# cyclops_r3p1.net
KiCad netlist of a schematic drawn in EAGLE
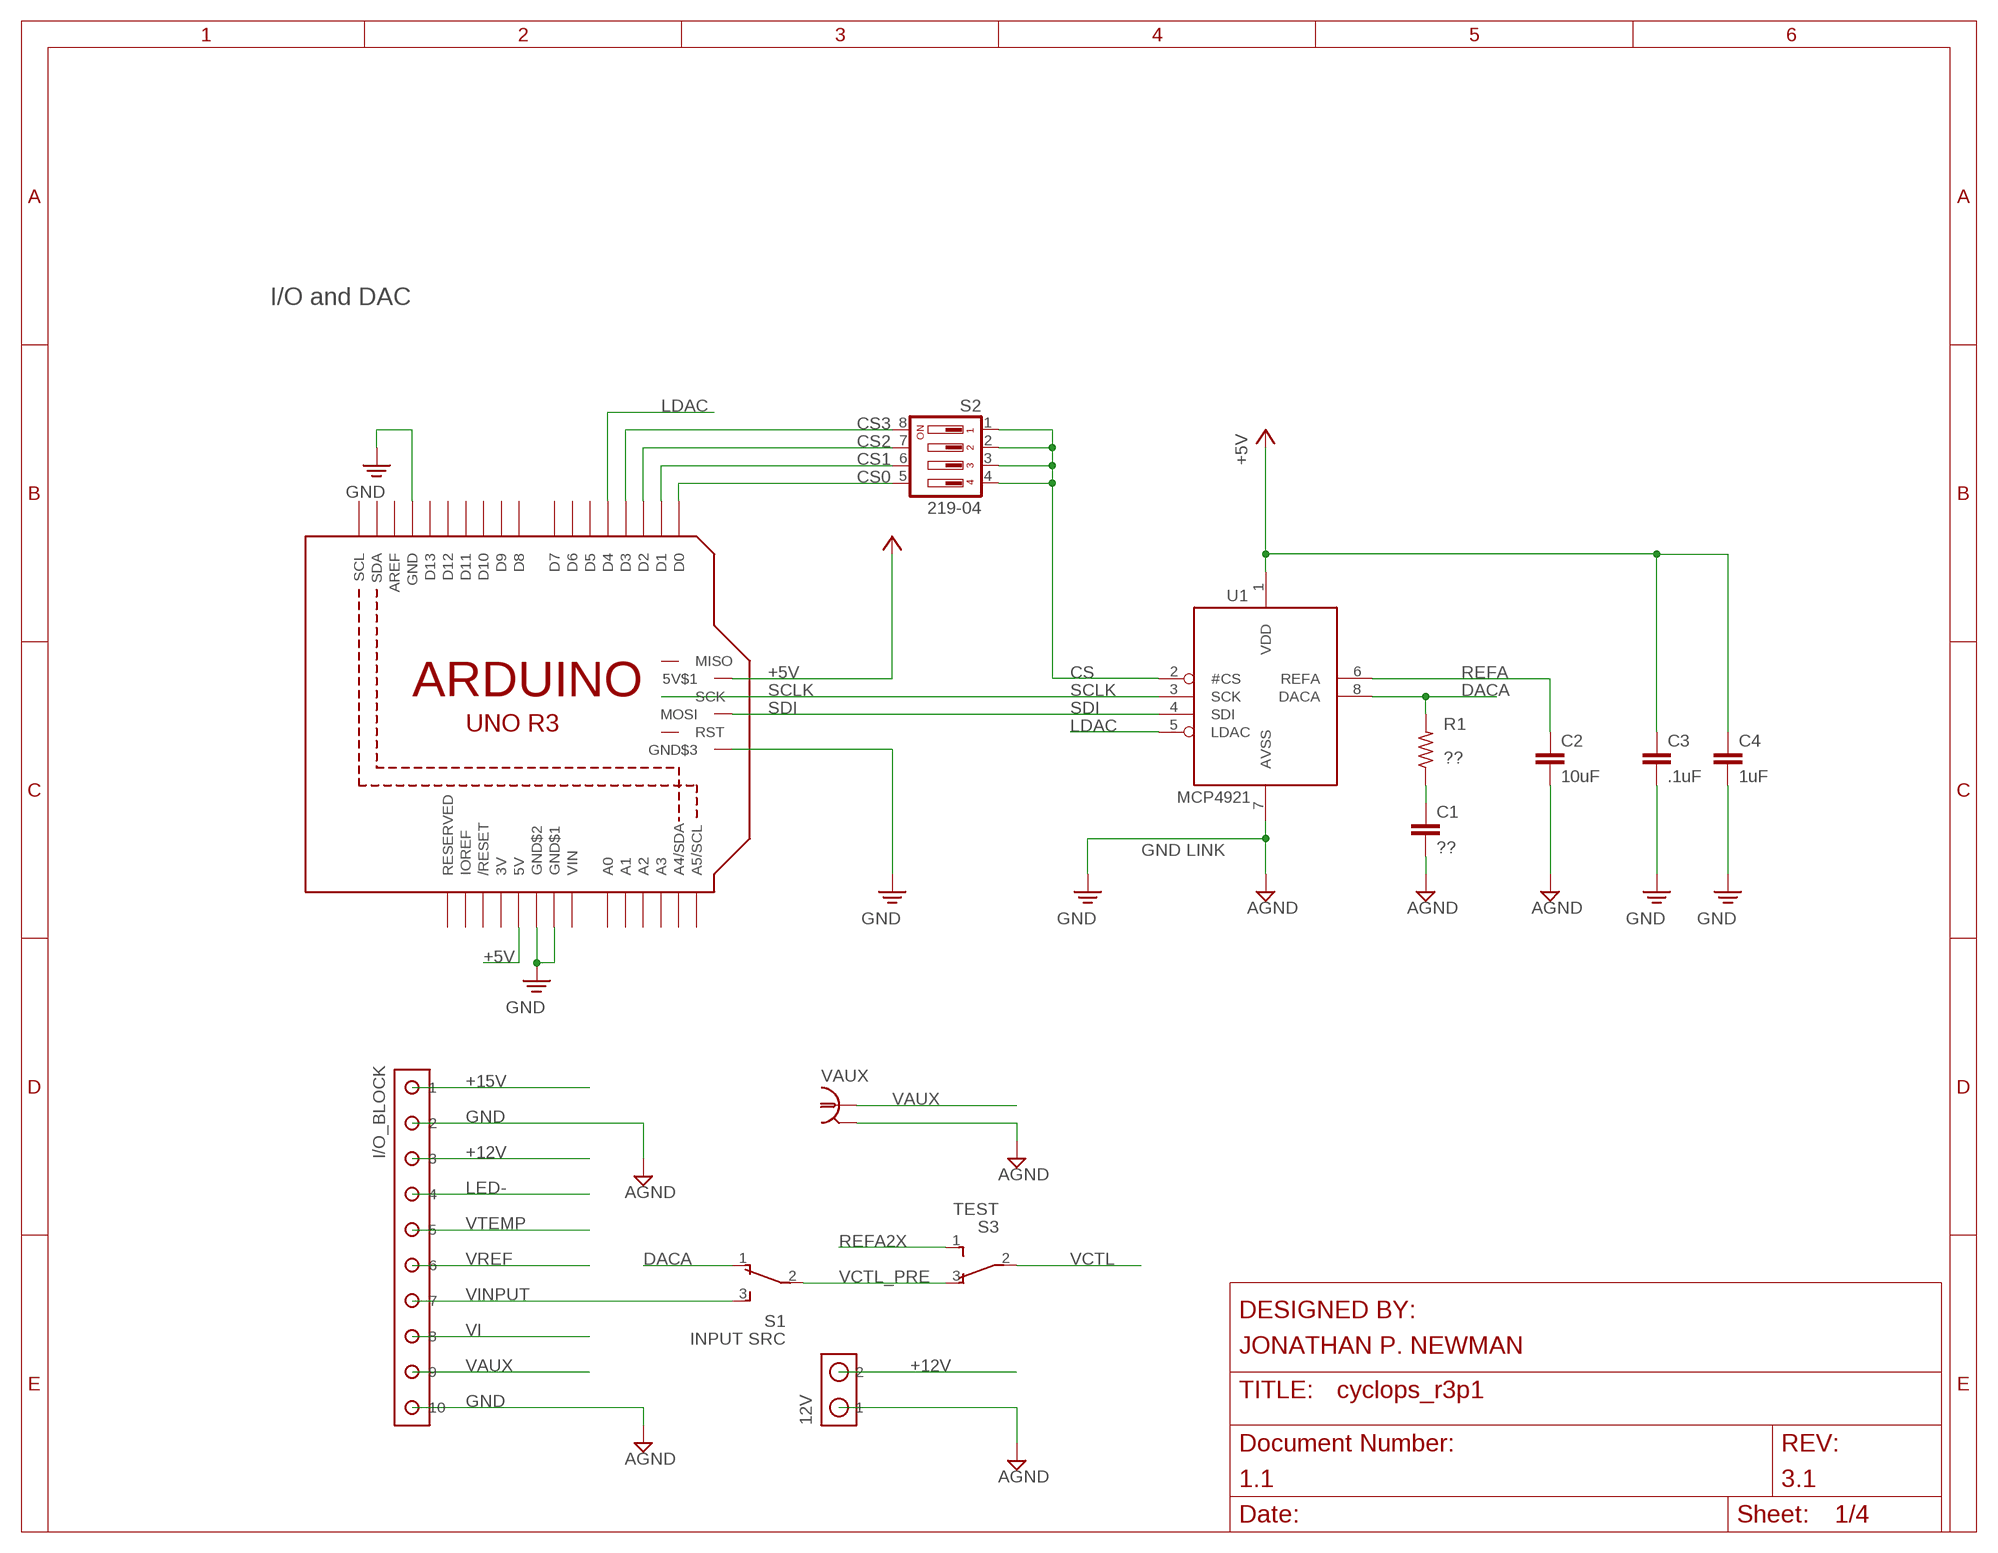
[diagram p0: schematic, sheet 1]
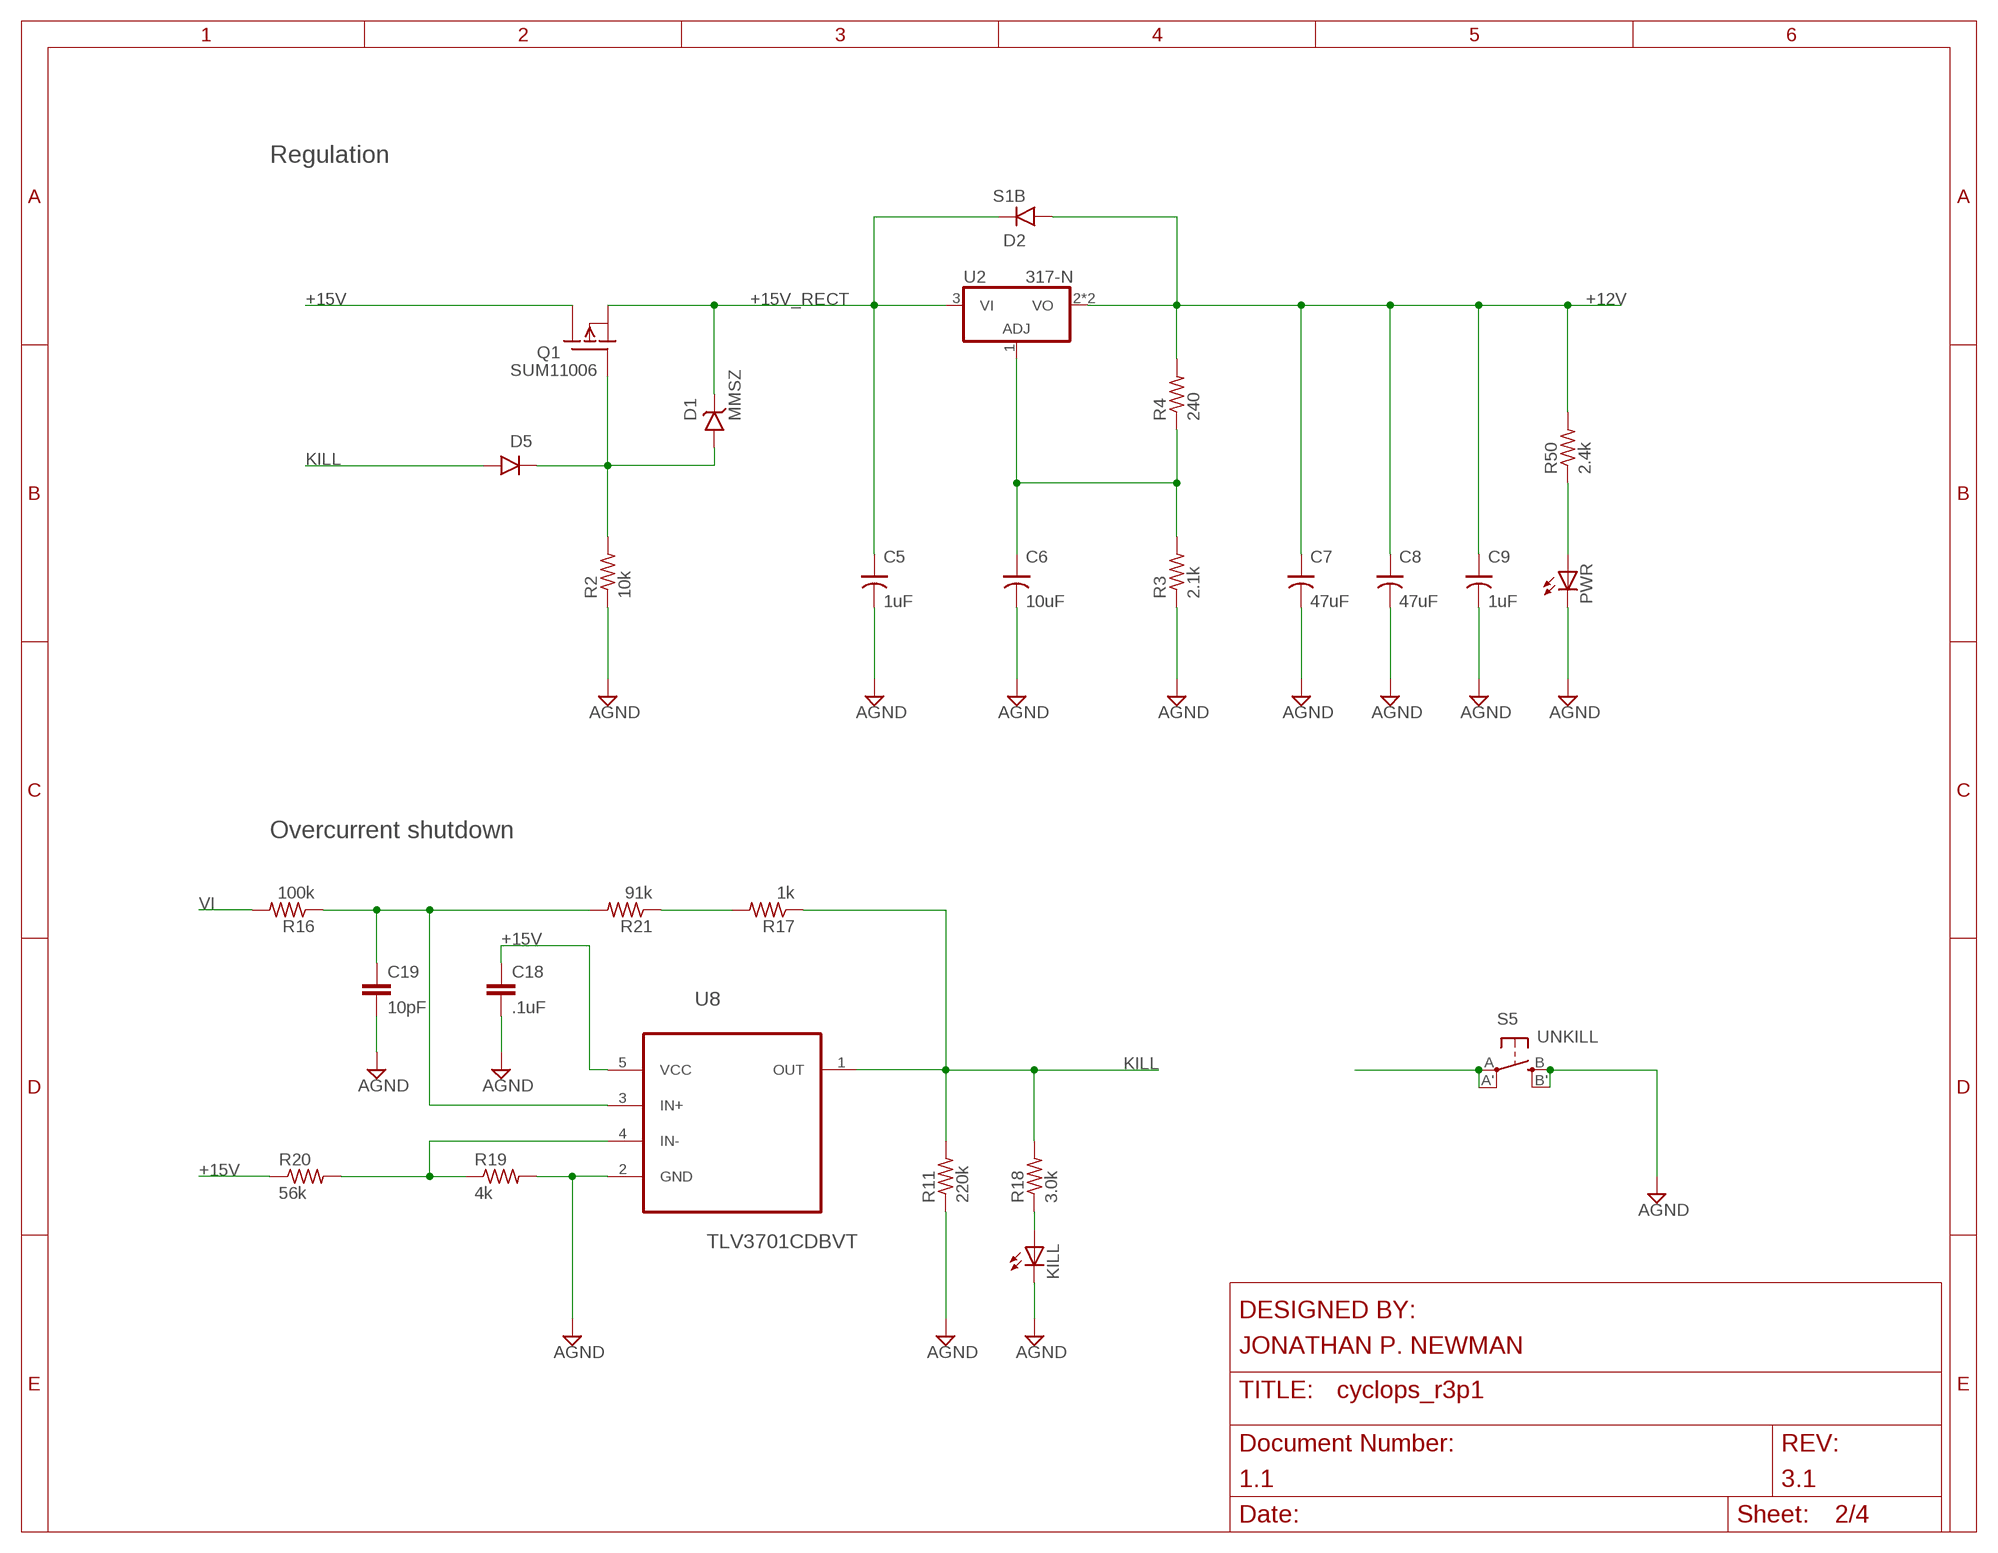
[diagram p1: schematic, sheet 2]
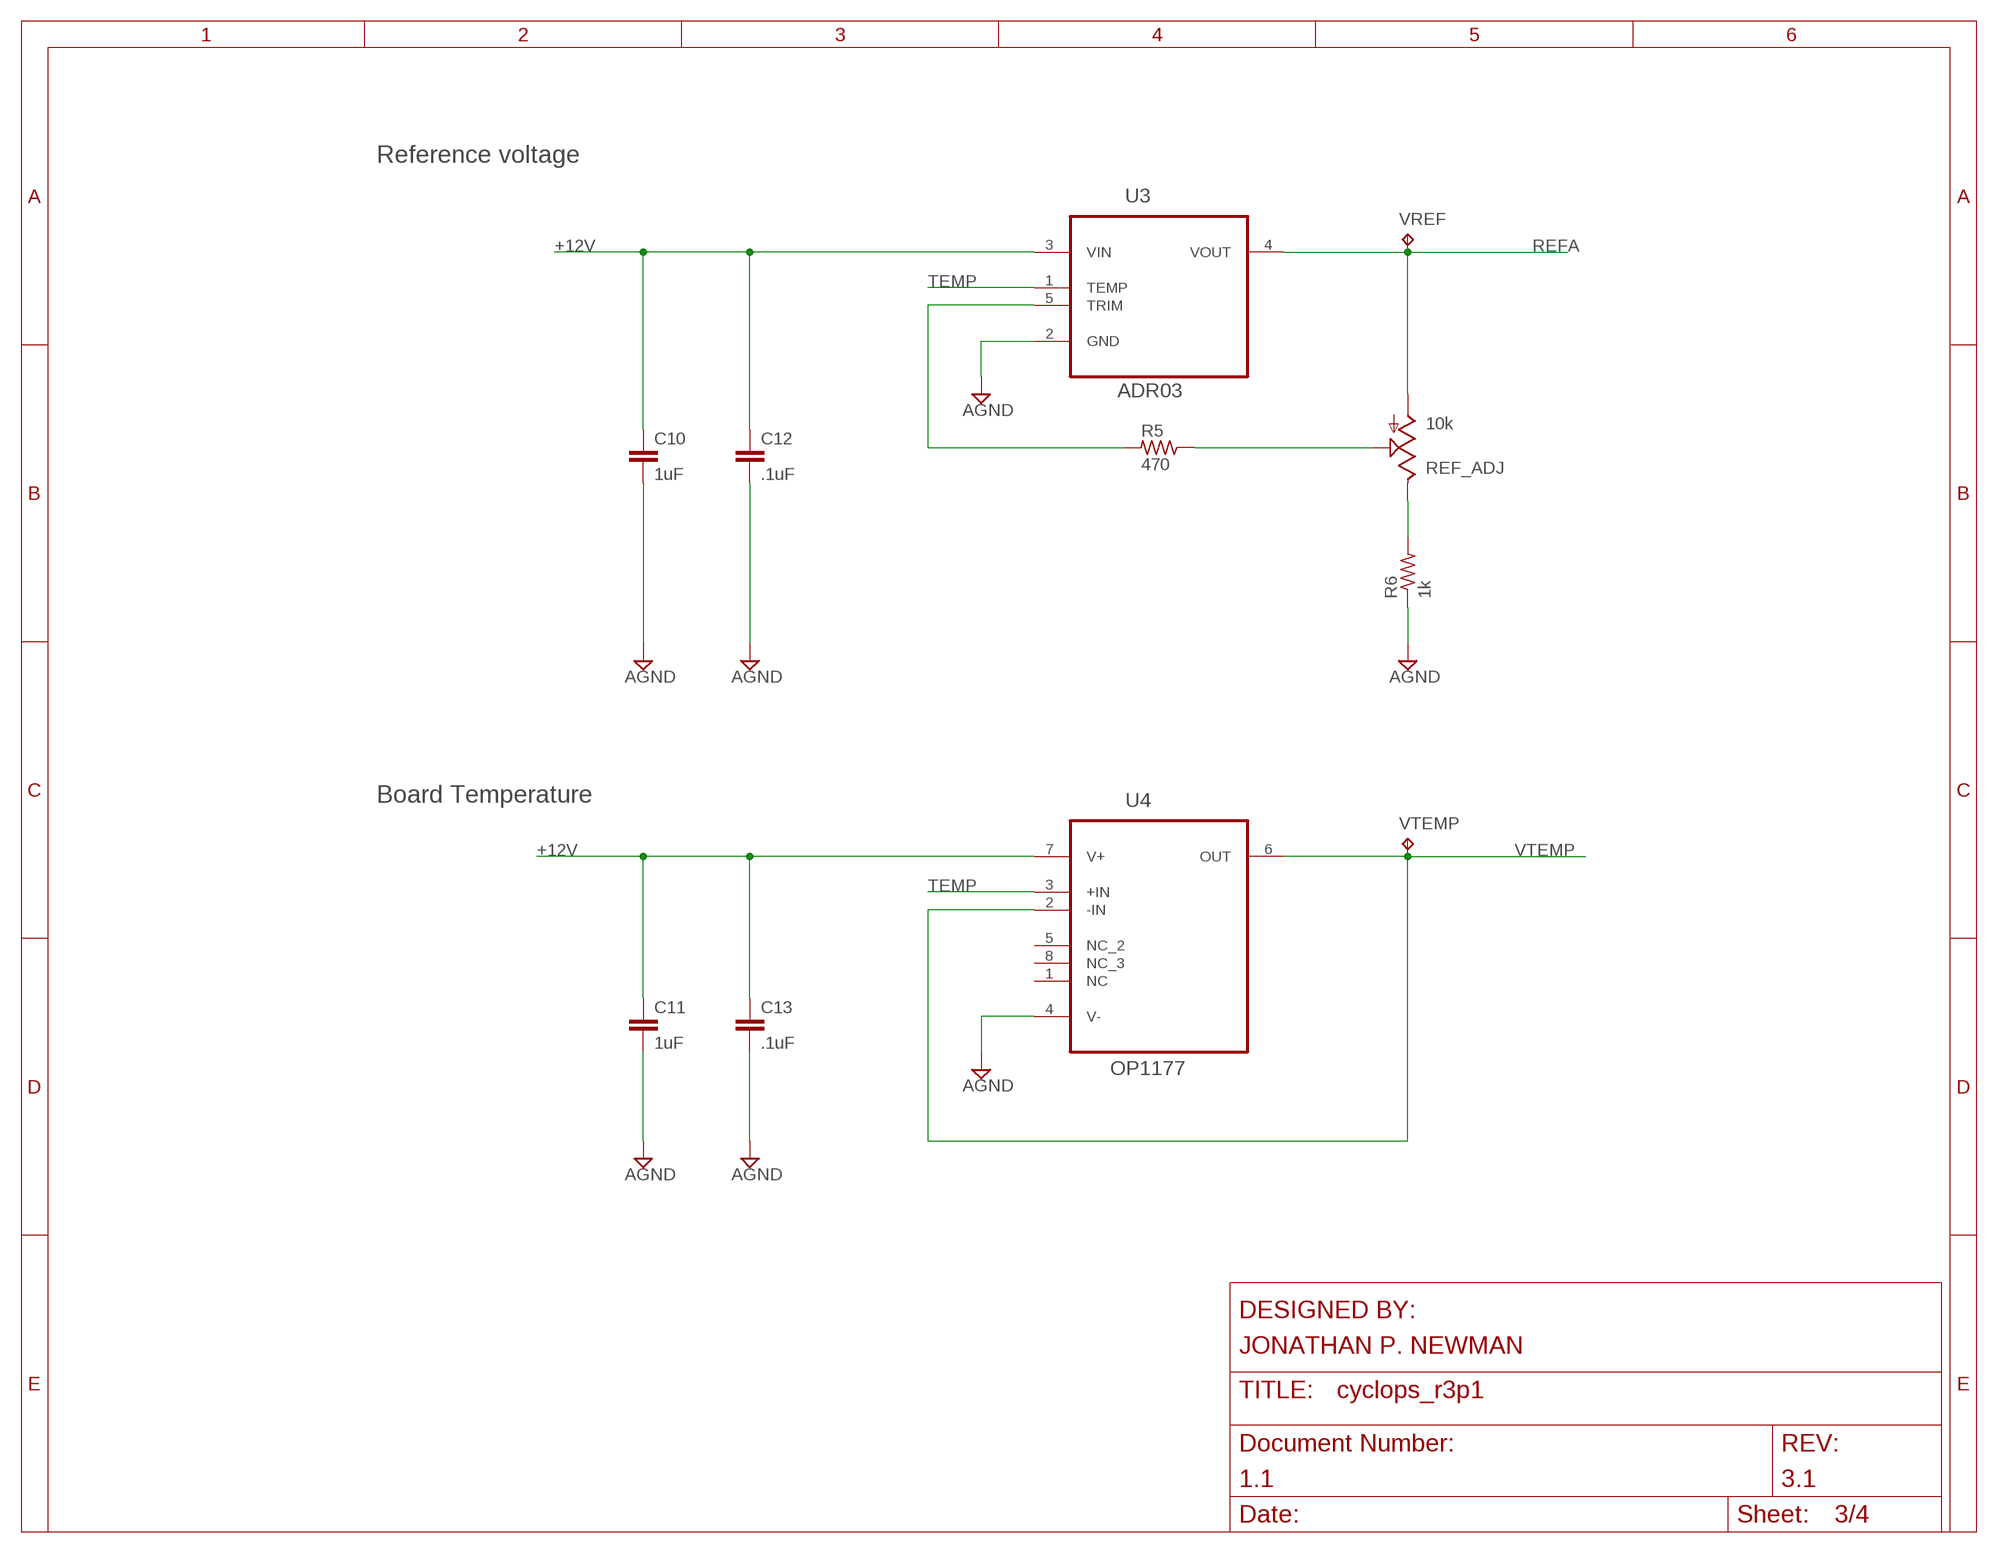
[diagram p2: schematic, sheet 3]
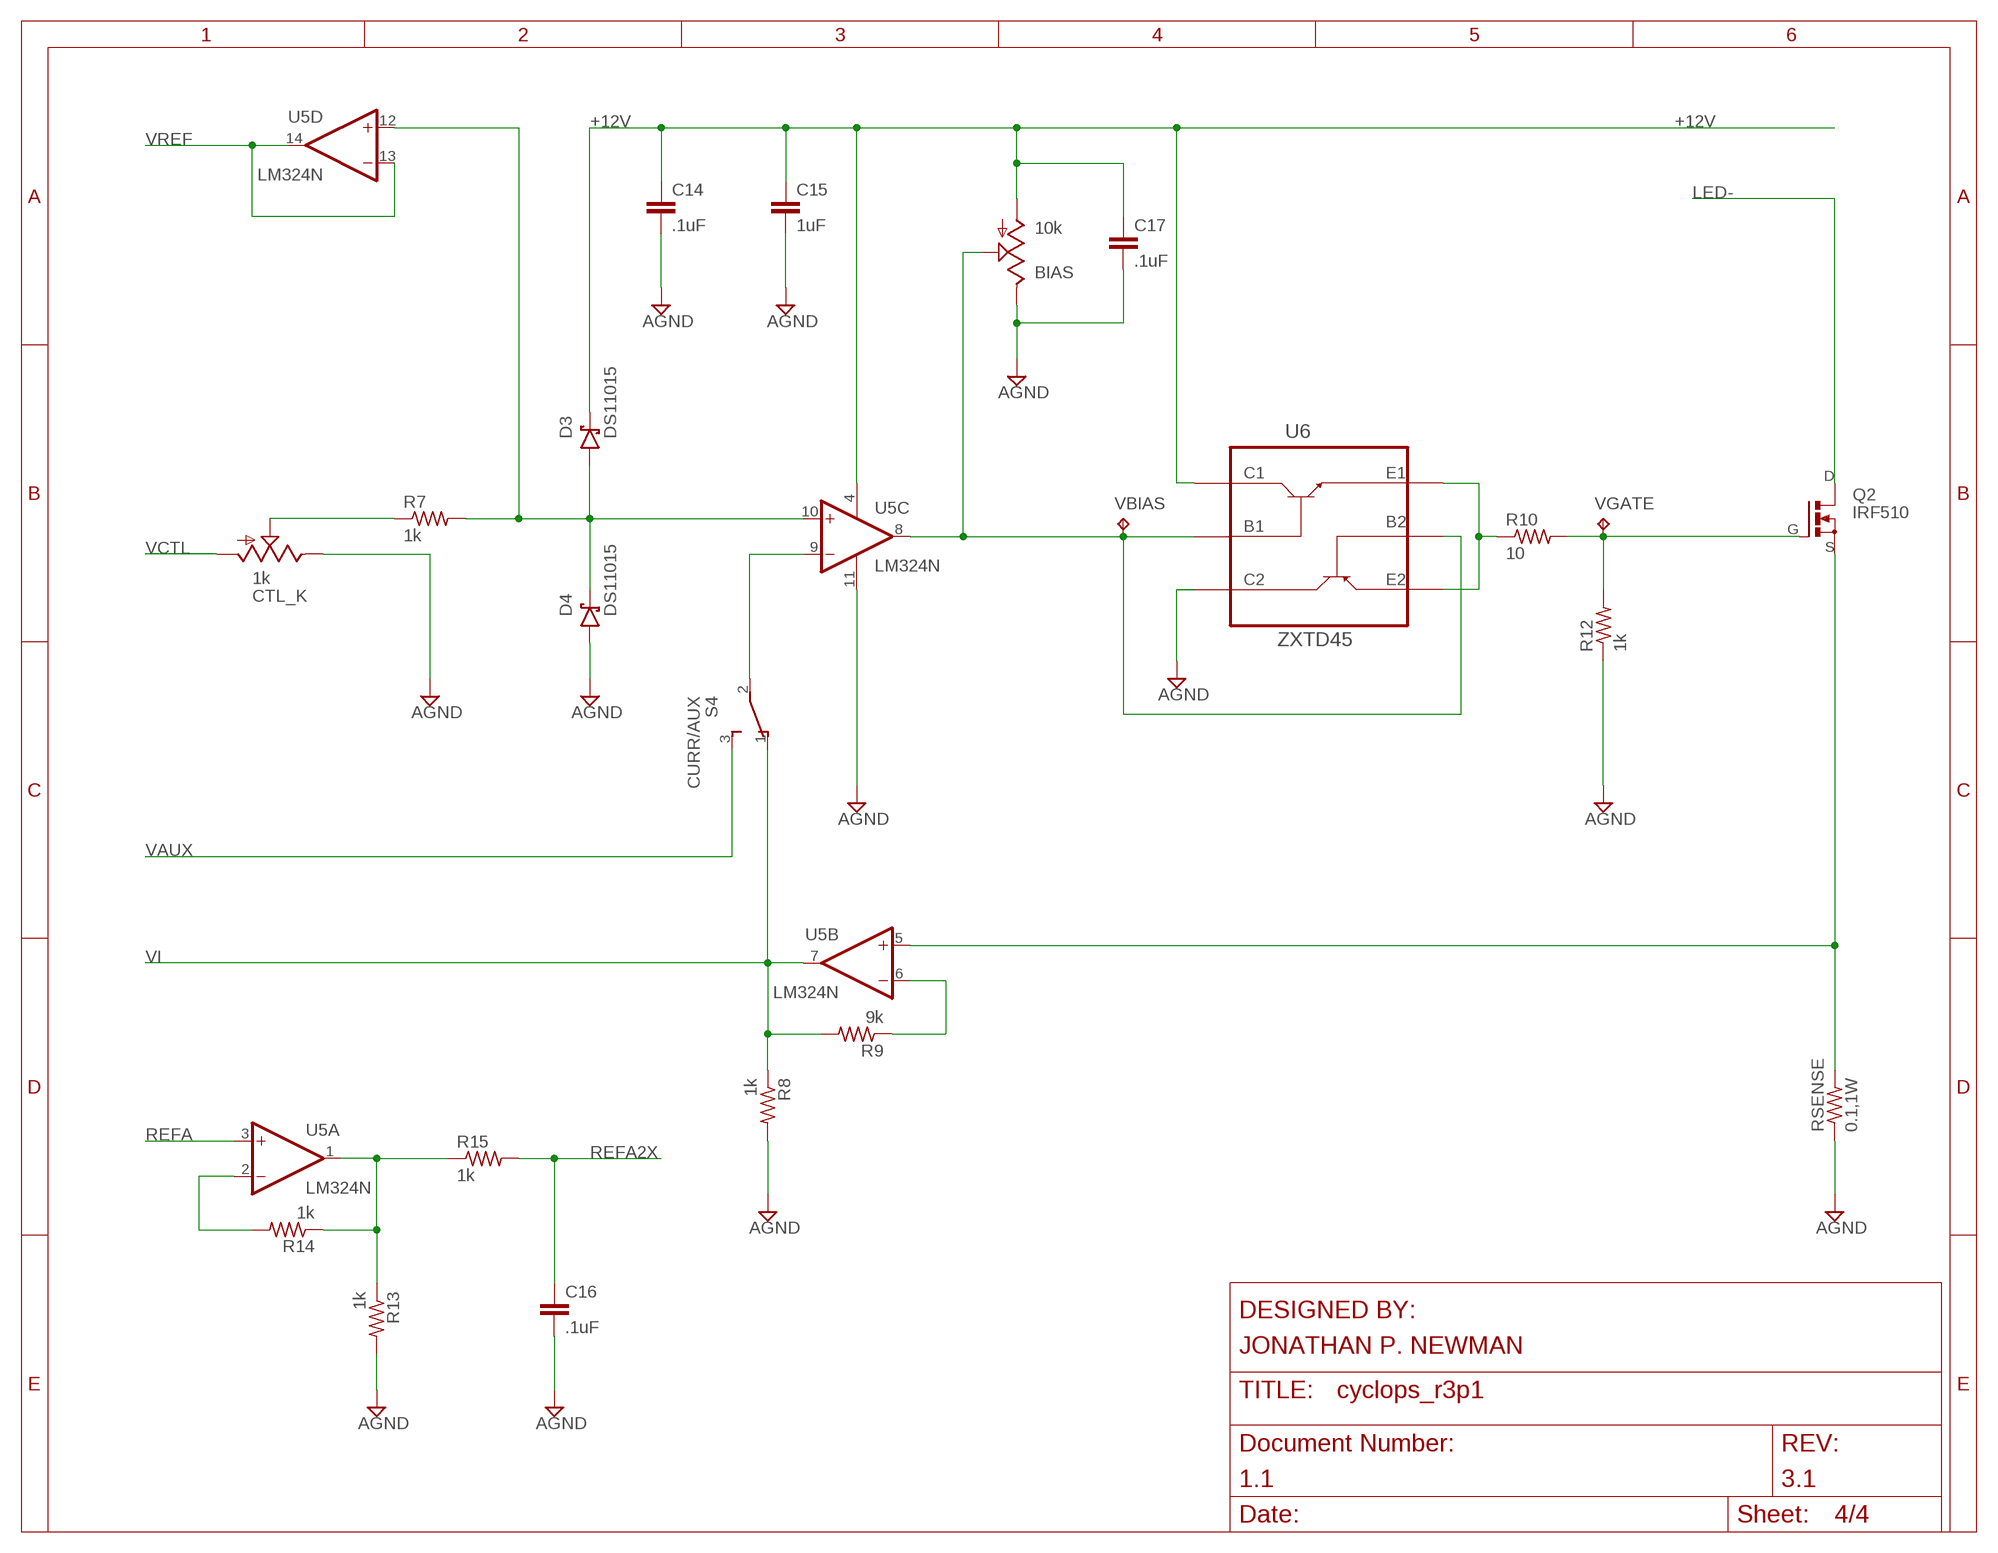
[diagram p3: schematic, sheet 4]

(export (version "E")
  (design (tool "Eeschema 10.0.6"))
  (components
    (comp (ref "C5")
      (value "1uF")
      (footprint "eagle-import:1206-POL")
      (libsource (lib "eagle-import") (part "C-POL_1206"))
    )
    (comp (ref "C6")
      (value "10uF")
      (footprint "eagle-import:1206-POL")
      (libsource (lib "eagle-import") (part "C-POL_1206"))
    )
    (comp (ref "C7")
      (value "47uF")
      (footprint "eagle-import:153CLV-0807")
      (libsource (lib "eagle-import") (part "C-POL_0807"))
    )
    (comp (ref "C8")
      (value "47uF")
      (footprint "eagle-import:153CLV-0807")
      (libsource (lib "eagle-import") (part "C-POL_0807"))
    )
    (comp (ref "C9")
      (value "1uF")
      (footprint "eagle-import:1206-POL")
      (libsource (lib "eagle-import") (part "C-POL_1206"))
    )
    (comp (ref "C18")
      (value ".1uF")
      (footprint "eagle-import:0603")
      (libsource (lib "eagle-import") (part "C_0603"))
    )
    (comp (ref "C19")
      (value "10pF")
      (footprint "eagle-import:0603")
      (libsource (lib "eagle-import") (part "C_0603"))
    )
    (comp (ref "D1")
      (value "MMSZ")
      (footprint "eagle-import:SOD123")
      (libsource (lib "eagle-import") (part "Z-DIODE_MMSZ"))
    )
    (comp (ref "D2")
      (value "S1B")
      (footprint "eagle-import:SMA-DO214AC")
      (libsource (lib "eagle-import") (part "DIODES1B-13-F"))
    )
    (comp (ref "D5")
      (value "DIODESOD-323")
      (footprint "eagle-import:SOD-323F")
      (libsource (lib "eagle-import") (part "DIODESOD-323"))
    )
    (comp (ref "KILL")
      (value "LEDYELLOW_0805")
      (footprint "eagle-import:CHIP-LED0805")
      (fields (field (name "MPN") "Dialight"))
      (libsource (lib "eagle-import") (part "LED_0805YELLOW"))
    )
    (comp (ref "PWR")
      (value "LEDYELLOW_0805")
      (footprint "eagle-import:CHIP-LED0805")
      (fields (field (name "MPN") "Dialight"))
      (libsource (lib "eagle-import") (part "LED_0805YELLOW"))
    )
    (comp (ref "Q1")
      (value "SUM11006")
      (footprint "eagle-import:TO-262_01")
      (libsource (lib "eagle-import") (part "SUM110P06_TO-262"))
    )
    (comp (ref "R2")
      (value "10k")
      (footprint "eagle-import:0603")
      (fields (field (name "MPN") "ERJ-3EKFxxxxV"))
      (libsource (lib "eagle-import") (part "R_0603"))
    )
    (comp (ref "R3")
      (value "2.1k")
      (footprint "eagle-import:0603")
      (fields (field (name "MPN") "ERJ-3EKFxxxxV"))
      (libsource (lib "eagle-import") (part "R_0603"))
    )
    (comp (ref "R4")
      (value "240")
      (footprint "eagle-import:0603")
      (fields (field (name "MPN") "ERJ-3EKFxxxxV"))
      (libsource (lib "eagle-import") (part "R_0603"))
    )
    (comp (ref "R11")
      (value "220k")
      (footprint "eagle-import:0603")
      (fields (field (name "MPN") "ERJ-3EKFxxxxV"))
      (libsource (lib "eagle-import") (part "R_0603"))
    )
    (comp (ref "R16")
      (value "100k")
      (footprint "eagle-import:0603")
      (fields (field (name "MPN") "ERJ-3EKFxxxxV"))
      (libsource (lib "eagle-import") (part "R_0603"))
    )
    (comp (ref "R17")
      (value "1k")
      (footprint "eagle-import:0603")
      (fields (field (name "MPN") "ERJ-3EKFxxxxV"))
      (libsource (lib "eagle-import") (part "R_0603"))
    )
    (comp (ref "R18")
      (value "3.0k")
      (footprint "eagle-import:0603")
      (fields (field (name "MPN") "ERJ-3EKFxxxxV"))
      (libsource (lib "eagle-import") (part "R_0603"))
    )
    (comp (ref "R19")
      (value "4k")
      (footprint "eagle-import:0603")
      (fields (field (name "MPN") "ERJ-3EKFxxxxV"))
      (libsource (lib "eagle-import") (part "R_0603"))
    )
    (comp (ref "R20")
      (value "56k")
      (footprint "eagle-import:0603")
      (fields (field (name "MPN") "ERJ-3EKFxxxxV"))
      (libsource (lib "eagle-import") (part "R_0603"))
    )
    (comp (ref "R21")
      (value "91k")
      (footprint "eagle-import:0603")
      (fields (field (name "MPN") "ERJ-3EKFxxxxV"))
      (libsource (lib "eagle-import") (part "R_0603"))
    )
    (comp (ref "R50")
      (value "2.4k")
      (footprint "eagle-import:0603")
      (fields (field (name "MPN") "ERJ-3EKFxxxxV"))
      (libsource (lib "eagle-import") (part "R_0603"))
    )
    (comp (ref "S5")
      (value "UNKILL")
      (footprint "eagle-import:EVQ-Q2")
      (libsource (lib "eagle-import") (part "SPST_TACT-EVQQ2"))
    )
    (comp (ref "U2")
      (value "317-N")
      (footprint "eagle-import:TO-263")
      (libsource (lib "eagle-import") (part "317_TO263"))
    )
    (comp (ref "U8")
      (value "TLV3701CDBVT")
      (footprint "eagle-import:SOT95P280X145-5N")
      (libsource (lib "eagle-import") (part "TLV3701CDBVT"))
    )
    (comp (ref "BIAS")
      (value "10k")
      (footprint "eagle-import:SM-42_43W")
      (libsource (lib "eagle-import") (part "TRIM_US-SM-42/43W"))
    )
    (comp (ref "C14")
      (value ".1uF")
      (footprint "eagle-import:0603")
      (libsource (lib "eagle-import") (part "C_0603"))
    )
    (comp (ref "C15")
      (value "1uF")
      (footprint "eagle-import:0805")
      (fields (field (name "PARTNO") "C2012X5R1Cxxxxxxx"))
      (libsource (lib "eagle-import") (part "C_0805"))
    )
    (comp (ref "C16")
      (value ".1uF")
      (footprint "eagle-import:0603")
      (libsource (lib "eagle-import") (part "C_0603"))
    )
    (comp (ref "C17")
      (value ".1uF")
      (footprint "eagle-import:0603")
      (libsource (lib "eagle-import") (part "C_0603"))
    )
    (comp (ref "CTL_K")
      (value "1k")
      (footprint "eagle-import:SM-42_43A")
      (libsource (lib "eagle-import") (part "TRIM_US-SM-42/43A"))
    )
    (comp (ref "D3")
      (value "DS11015")
      (footprint "eagle-import:SOD123")
      (libsource (lib "eagle-import") (part "S-DIODESOD-123"))
    )
    (comp (ref "D4")
      (value "DS11015")
      (footprint "eagle-import:SOD123")
      (libsource (lib "eagle-import") (part "S-DIODESOD-123"))
    )
    (comp (ref "Q2")
      (value "IRF510")
      (footprint "eagle-import:TO-262_01")
      (libsource (lib "eagle-import") (part "N-MOSFETTO-262"))
    )
    (comp (ref "R7")
      (value "1k")
      (footprint "eagle-import:0603")
      (fields (field (name "MPN") "ERJ-3EKFxxxxV"))
      (libsource (lib "eagle-import") (part "R_0603"))
    )
    (comp (ref "R8")
      (value "1k")
      (footprint "eagle-import:0603")
      (fields (field (name "MPN") "ERJ-3EKFxxxxV"))
      (libsource (lib "eagle-import") (part "R_0603"))
    )
    (comp (ref "R9")
      (value "9k")
      (footprint "eagle-import:0603")
      (fields (field (name "MPN") "ERJ-3EKFxxxxV"))
      (libsource (lib "eagle-import") (part "R_0603"))
    )
    (comp (ref "R10")
      (value "10")
      (footprint "eagle-import:0603")
      (fields (field (name "MPN") "ERJ-3EKFxxxxV"))
      (libsource (lib "eagle-import") (part "R_0603"))
    )
    (comp (ref "R12")
      (value "1k")
      (footprint "eagle-import:0603")
      (fields (field (name "MPN") "ERJ-3EKFxxxxV"))
      (libsource (lib "eagle-import") (part "R_0603"))
    )
    (comp (ref "R13")
      (value "1k")
      (footprint "eagle-import:0603")
      (fields (field (name "MPN") "ERJ-3EKFxxxxV"))
      (libsource (lib "eagle-import") (part "R_0603"))
    )
    (comp (ref "R14")
      (value "1k")
      (footprint "eagle-import:0603")
      (fields (field (name "MPN") "ERJ-3EKFxxxxV"))
      (libsource (lib "eagle-import") (part "R_0603"))
    )
    (comp (ref "R15")
      (value "1k")
      (footprint "eagle-import:0603")
      (fields (field (name "MPN") "ERJ-3EKFxxxxV"))
      (libsource (lib "eagle-import") (part "R_0603"))
    )
    (comp (ref "RSENSE")
      (value "0.1,1W")
      (footprint "eagle-import:2512")
      (libsource (lib "eagle-import") (part "R_2512"))
    )
    (comp (ref "S4")
      (value "CURR/AUX")
      (footprint "eagle-import:PCM12")
      (libsource (lib "eagle-import") (part "SPDT_PCM12"))
    )
    (comp (ref "U5")
      (value "LM324N")
      (footprint "eagle-import:SO14")
      (libsource (lib "eagle-import") (part "LM324D"))
    )
    (comp (ref "U6")
      (value "ZXTD45")
      (footprint "eagle-import:SOT23-6")
      (libsource (lib "eagle-import") (part "ZXTD4591E6"))
    )
    (comp (ref "VBIAS")
      (value "TPTP08R")
      (footprint "eagle-import:TP08R")
      (libsource (lib "eagle-import") (part "TPTP08R"))
    )
    (comp (ref "VGATE")
      (value "TPTP08R")
      (footprint "eagle-import:TP08R")
      (libsource (lib "eagle-import") (part "TPTP08R"))
    )
    (comp (ref "12V")
      (value "SCREW2")
      (footprint "eagle-import:SCREW2")
      (libsource (lib "eagle-import") (part "SCREW2"))
    )
    (comp (ref "C1")
      (value "??")
      (footprint "eagle-import:0603")
      (libsource (lib "eagle-import") (part "C_0603"))
    )
    (comp (ref "C2")
      (value "10uF")
      (footprint "eagle-import:0805")
      (fields (field (name "PARTNO") "C2012X5R1Cxxxxxxx"))
      (libsource (lib "eagle-import") (part "C_0805"))
    )
    (comp (ref "C3")
      (value ".1uF")
      (footprint "eagle-import:0603")
      (libsource (lib "eagle-import") (part "C_0603"))
    )
    (comp (ref "C4")
      (value "1uF")
      (footprint "eagle-import:0805")
      (fields (field (name "PARTNO") "C2012X5R1Cxxxxxxx"))
      (libsource (lib "eagle-import") (part "C_0805"))
    )
    (comp (ref "I/O_BLOCK")
      (value "SCREW10_0.1-THRU")
      (footprint "eagle-import:SCREW10")
      (libsource (lib "eagle-import") (part "SCREW10_0.1-THRU"))
    )
    (comp (ref "R1")
      (value "??")
      (footprint "eagle-import:0603")
      (fields (field (name "MPN") "ERJ-3EKFxxxxV"))
      (libsource (lib "eagle-import") (part "R_0603"))
    )
    (comp (ref "S1")
      (value "INPUT SRC")
      (footprint "eagle-import:PCM12")
      (libsource (lib "eagle-import") (part "SPDT_PCM12"))
    )
    (comp (ref "S2")
      (value "219-04")
      (footprint "eagle-import:CTS-219-04")
      (libsource (lib "eagle-import") (part "219-04"))
    )
    (comp (ref "S3")
      (value "TEST")
      (footprint "eagle-import:CFPA")
      (libsource (lib "eagle-import") (part "SPDT_CFPA"))
    )
    (comp (ref "U$1")
      (value "ARDUINO_R3_ICSP")
      (footprint "eagle-import:ARDUINOR3_ICSP")
      (libsource (lib "eagle-import") (part "ARDUINO_R3_ICSP"))
    )
    (comp (ref "U1")
      (value "MCP4921")
      (footprint "eagle-import:SO08")
      (libsource (lib "eagle-import") (part "MCP4921SOIC"))
    )
    (comp (ref "VAUX")
      (value "BNC_V-BITE")
      (footprint "eagle-import:361V509E")
      (libsource (lib "eagle-import") (part "BNC_V-BITE"))
    )
    (comp (ref "C10")
      (value "1uF")
      (footprint "eagle-import:0805")
      (fields (field (name "PARTNO") "C2012X5R1Cxxxxxxx"))
      (libsource (lib "eagle-import") (part "C_0805"))
    )
    (comp (ref "C11")
      (value "1uF")
      (footprint "eagle-import:0805")
      (fields (field (name "PARTNO") "C2012X5R1Cxxxxxxx"))
      (libsource (lib "eagle-import") (part "C_0805"))
    )
    (comp (ref "C12")
      (value ".1uF")
      (footprint "eagle-import:0603")
      (libsource (lib "eagle-import") (part "C_0603"))
    )
    (comp (ref "C13")
      (value ".1uF")
      (footprint "eagle-import:0603")
      (libsource (lib "eagle-import") (part "C_0603"))
    )
    (comp (ref "R5")
      (value "470")
      (footprint "eagle-import:0603")
      (fields (field (name "MPN") "ERJ-3EKFxxxxV"))
      (libsource (lib "eagle-import") (part "R_0603"))
    )
    (comp (ref "R6")
      (value "1k")
      (footprint "eagle-import:0603")
      (fields (field (name "MPN") "ERJ-3EKFxxxxV"))
      (libsource (lib "eagle-import") (part "R_0603"))
    )
    (comp (ref "REF_ADJ")
      (value "10k")
      (footprint "eagle-import:SM-42_43W")
      (libsource (lib "eagle-import") (part "TRIM_US-SM-42/43W"))
    )
    (comp (ref "U3")
      (value "ADR03")
      (footprint "eagle-import:SOT65P210X110-5N")
      (fields (field (name "MPN") "ADR03AKSZ-REEL7"))
      (libsource (lib "eagle-import") (part "ADR03AKSZ-REEL7"))
    )
    (comp (ref "U4")
      (value "OP1177")
      (footprint "eagle-import:SOP65P490X110-8N")
      (fields (field (name "MPN") "OP1177ARMZ"))
      (libsource (lib "eagle-import") (part "OP1177ARMZ"))
    )
    (comp (ref "VREF")
      (value "TPTP08R")
      (footprint "eagle-import:TP08R")
      (libsource (lib "eagle-import") (part "TPTP08R"))
    )
    (comp (ref "VTEMP")
      (value "TPTP08R")
      (footprint "eagle-import:TP08R")
      (libsource (lib "eagle-import") (part "TPTP08R"))
    )
  )
  (nets
    (net (code "1") (name "+5V") (class "Default")
      (node (ref "C3") (pin "1") (pinfunction "1_1") (pintype "passive"))
      (node (ref "C4") (pin "1") (pinfunction "1_1") (pintype "passive"))
      (node (ref "U$1") (pin "+5V") (pinfunction "5V_+5V") (pintype "power_in"))
      (node (ref "U$1") (pin "5V") (pinfunction "5V$1_5V") (pintype "passive"))
      (node (ref "U1") (pin "1") (pinfunction "VDD_1") (pintype "power_in"))
    )
    (net (code "2") (name "+12V") (class "Default")
      (node (ref "12V") (pin "P$2") (pinfunction "2_P$2") (pintype "passive"))
      (node (ref "BIAS") (pin "1") (pinfunction "A_1") (pintype "passive"))
      (node (ref "C10") (pin "1") (pinfunction "1_1") (pintype "passive"))
      (node (ref "C11") (pin "1") (pinfunction "1_1") (pintype "passive"))
      (node (ref "C12") (pin "1") (pinfunction "1_1") (pintype "passive"))
      (node (ref "C13") (pin "1") (pinfunction "1_1") (pintype "passive"))
      (node (ref "C14") (pin "1") (pinfunction "1_1") (pintype "passive"))
      (node (ref "C15") (pin "1") (pinfunction "1_1") (pintype "passive"))
      (node (ref "C17") (pin "1") (pinfunction "1_1") (pintype "passive"))
      (node (ref "C7") (pin "+") (pinfunction "+_+") (pintype "passive"))
      (node (ref "C8") (pin "+") (pinfunction "+_+") (pintype "passive"))
      (node (ref "C9") (pin "+") (pinfunction "+_+") (pintype "passive"))
      (node (ref "D2") (pin "A") (pinfunction "A_A") (pintype "passive"))
      (node (ref "D3") (pin "C") (pinfunction "C_C") (pintype "passive"))
      (node (ref "I/O_BLOCK") (pin "P$3") (pinfunction "3_P$3") (pintype "bidirectional"))
      (node (ref "R4") (pin "2") (pinfunction "2_2") (pintype "passive"))
      (node (ref "R50") (pin "2") (pinfunction "2_2") (pintype "passive"))
      (node (ref "U2") (pin "2") (pinfunction "VO_2") (pintype "passive"))
      (node (ref "U2") (pin "4") (pinfunction "VO_4") (pintype "passive"))
      (node (ref "U3") (pin "3") (pinfunction "VIN_3") (pintype "power_in"))
      (node (ref "U4") (pin "7") (pinfunction "V+_7") (pintype "power_in"))
      (node (ref "U5") (pin "4") (pinfunction "V+_4") (pintype "power_in"))
      (node (ref "U6") (pin "1") (pinfunction "C1_1") (pintype "bidirectional"))
    )
    (net (code "3") (name "+15V") (class "Default")
      (node (ref "C18") (pin "1") (pinfunction "1_1") (pintype "passive"))
      (node (ref "I/O_BLOCK") (pin "P$1") (pinfunction "1_P$1") (pintype "bidirectional"))
      (node (ref "Q1") (pin "D") (pinfunction "D_D") (pintype "passive"))
      (node (ref "R20") (pin "1") (pinfunction "1_1") (pintype "passive"))
      (node (ref "U8") (pin "5") (pinfunction "VCC_5") (pintype "power_in"))
    )
    (net (code "4") (name "+15V_RECT") (class "Default")
      (node (ref "C5") (pin "+") (pinfunction "+_+") (pintype "passive"))
      (node (ref "D1") (pin "C") (pinfunction "C_C") (pintype "passive"))
      (node (ref "D2") (pin "C") (pinfunction "C_C") (pintype "passive"))
      (node (ref "Q1") (pin "S") (pinfunction "S_S") (pintype "passive"))
      (node (ref "U2") (pin "3") (pinfunction "VI_3") (pintype "input"))
    )
    (net (code "5") (name "3V") (class "Default")
      (node (ref "U$1") (pin "3V") (pinfunction "3V_3V") (pintype "power_in"))
    )
    (net (code "6") (name "COMP+") (class "Default")
      (node (ref "C19") (pin "1") (pinfunction "1_1") (pintype "passive"))
      (node (ref "R16") (pin "1") (pinfunction "1_1") (pintype "passive"))
      (node (ref "R21") (pin "2") (pinfunction "2_2") (pintype "passive"))
      (node (ref "S5") (pin "A") (pinfunction "P_A") (pintype "passive"))
      (node (ref "S5") (pin "A'") (pinfunction "P1_A'") (pintype "passive"))
      (node (ref "U8") (pin "3") (pinfunction "IN+_3") (pintype "input"))
    )
    (net (code "7") (name "CS") (class "Default")
      (node (ref "S2") (pin "1") (pinfunction "1_1") (pintype "passive"))
      (node (ref "S2") (pin "2") (pinfunction "2_2") (pintype "passive"))
      (node (ref "S2") (pin "3") (pinfunction "3_3") (pintype "passive"))
      (node (ref "S2") (pin "4") (pinfunction "4_4") (pintype "passive"))
      (node (ref "U1") (pin "2") (pinfunction "#CS_2") (pintype "input"))
    )
    (net (code "8") (name "CS0") (class "Default")
      (node (ref "S2") (pin "5") (pinfunction "5_5") (pintype "passive"))
      (node (ref "U$1") (pin "D0") (pinfunction "D0_D0") (pintype "bidirectional"))
    )
    (net (code "9") (name "CS1") (class "Default")
      (node (ref "S2") (pin "6") (pinfunction "6_6") (pintype "passive"))
      (node (ref "U$1") (pin "D1") (pinfunction "D1_D1") (pintype "bidirectional"))
    )
    (net (code "10") (name "CS2") (class "Default")
      (node (ref "S2") (pin "7") (pinfunction "7_7") (pintype "passive"))
      (node (ref "U$1") (pin "D2") (pinfunction "D2_D2") (pintype "bidirectional"))
    )
    (net (code "11") (name "CS3") (class "Default")
      (node (ref "S2") (pin "8") (pinfunction "8_8") (pintype "passive"))
      (node (ref "U$1") (pin "D3") (pinfunction "D3_D3") (pintype "bidirectional"))
    )
    (net (code "12") (name "DACA") (class "Default")
      (node (ref "R1") (pin "2") (pinfunction "2_2") (pintype "passive"))
      (node (ref "S1") (pin "1") (pinfunction "1_1") (pintype "passive"))
      (node (ref "U1") (pin "8") (pinfunction "DACA_8") (pintype "output"))
    )
    (net (code "13") (name "GND") (class "Default")
      (node (ref "12V") (pin "P$1") (pinfunction "1_P$1") (pintype "passive"))
      (node (ref "BIAS") (pin "3") (pinfunction "E_3") (pintype "passive"))
      (node (ref "C1") (pin "2") (pinfunction "2_2") (pintype "passive"))
      (node (ref "C10") (pin "2") (pinfunction "2_2") (pintype "passive"))
      (node (ref "C11") (pin "2") (pinfunction "2_2") (pintype "passive"))
      (node (ref "C12") (pin "2") (pinfunction "2_2") (pintype "passive"))
      (node (ref "C13") (pin "2") (pinfunction "2_2") (pintype "passive"))
      (node (ref "C14") (pin "2") (pinfunction "2_2") (pintype "passive"))
      (node (ref "C15") (pin "2") (pinfunction "2_2") (pintype "passive"))
      (node (ref "C16") (pin "2") (pinfunction "2_2") (pintype "passive"))
      (node (ref "C17") (pin "2") (pinfunction "2_2") (pintype "passive"))
      (node (ref "C18") (pin "2") (pinfunction "2_2") (pintype "passive"))
      (node (ref "C19") (pin "2") (pinfunction "2_2") (pintype "passive"))
      (node (ref "C2") (pin "2") (pinfunction "2_2") (pintype "passive"))
      (node (ref "C3") (pin "2") (pinfunction "2_2") (pintype "passive"))
      (node (ref "C4") (pin "2") (pinfunction "2_2") (pintype "passive"))
      (node (ref "C5") (pin "-") (pinfunction "-_-") (pintype "passive"))
      (node (ref "C6") (pin "-") (pinfunction "-_-") (pintype "passive"))
      (node (ref "C7") (pin "-") (pinfunction "-_-") (pintype "passive"))
      (node (ref "C8") (pin "-") (pinfunction "-_-") (pintype "passive"))
      (node (ref "C9") (pin "-") (pinfunction "-_-") (pintype "passive"))
      (node (ref "CTL_K") (pin "3") (pinfunction "E_3") (pintype "passive"))
      (node (ref "D4") (pin "A") (pinfunction "A_A") (pintype "passive"))
      (node (ref "I/O_BLOCK") (pin "P$10") (pinfunction "10_P$10") (pintype "bidirectional"))
      (node (ref "I/O_BLOCK") (pin "P$2") (pinfunction "2_P$2") (pintype "bidirectional"))
      (node (ref "KILL") (pin "C") (pinfunction "C_C") (pintype "passive"))
      (node (ref "PWR") (pin "C") (pinfunction "C_C") (pintype "passive"))
      (node (ref "R11") (pin "1") (pinfunction "1_1") (pintype "passive"))
      (node (ref "R12") (pin "1") (pinfunction "1_1") (pintype "passive"))
      (node (ref "R13") (pin "2") (pinfunction "2_2") (pintype "passive"))
      (node (ref "R19") (pin "2") (pinfunction "2_2") (pintype "passive"))
      (node (ref "R2") (pin "1") (pinfunction "1_1") (pintype "passive"))
      (node (ref "R3") (pin "1") (pinfunction "1_1") (pintype "passive"))
      (node (ref "R6") (pin "1") (pinfunction "1_1") (pintype "passive"))
      (node (ref "R8") (pin "2") (pinfunction "2_2") (pintype "passive"))
      (node (ref "RSENSE") (pin "1") (pinfunction "1_1") (pintype "passive"))
      (node (ref "S5") (pin "B") (pinfunction "S_B") (pintype "passive"))
      (node (ref "S5") (pin "B'") (pinfunction "S1_B'") (pintype "passive"))
      (node (ref "U$1") (pin "GND") (pinfunction "GND_GND") (pintype "power_in"))
      (node (ref "U$1") (pin "GND$1") (pinfunction "GND$1_GND$1") (pintype "power_in"))
      (node (ref "U$1") (pin "GND$2") (pinfunction "GND$2_GND$2") (pintype "power_in"))
      (node (ref "U$1") (pin "GND$3") (pinfunction "GND$3_GND$3") (pintype "passive"))
      (node (ref "U1") (pin "7") (pinfunction "AVSS_7") (pintype "power_in"))
      (node (ref "U3") (pin "2") (pinfunction "GND_2") (pintype "passive"))
      (node (ref "U4") (pin "4") (pinfunction "V-_4") (pintype "power_in"))
      (node (ref "U5") (pin "11") (pinfunction "V-_11") (pintype "power_in"))
      (node (ref "U6") (pin "3") (pinfunction "C2_3") (pintype "bidirectional"))
      (node (ref "U8") (pin "2") (pinfunction "GND_2") (pintype "passive"))
      (node (ref "VAUX") (pin "2") (pinfunction "2_2") (pintype "passive"))
      (node (ref "VAUX") (pin "3") (pinfunction "2_3") (pintype "passive"))
    )
    (net (code "14") (name "KILL") (class "Default")
      (node (ref "D5") (pin "A") (pinfunction "A_A") (pintype "passive"))
      (node (ref "R11") (pin "2") (pinfunction "2_2") (pintype "passive"))
      (node (ref "R17") (pin "1") (pinfunction "1_1") (pintype "passive"))
      (node (ref "R18") (pin "2") (pinfunction "2_2") (pintype "passive"))
      (node (ref "U8") (pin "1") (pinfunction "OUT_1") (pintype "output"))
    )
    (net (code "15") (name "LDAC") (class "Default")
      (node (ref "U$1") (pin "D4") (pinfunction "D4_D4") (pintype "bidirectional"))
      (node (ref "U1") (pin "5") (pinfunction "LDAC_5") (pintype "input"))
    )
    (net (code "16") (name "LED-") (class "Default")
      (node (ref "I/O_BLOCK") (pin "P$4") (pinfunction "4_P$4") (pintype "bidirectional"))
      (node (ref "Q2") (pin "D") (pinfunction "D_D") (pintype "bidirectional"))
    )
    (net (code "17") (name "Net-(BIAS-S)") (class "Default")
      (node (ref "BIAS") (pin "2") (pinfunction "S_2") (pintype "passive"))
      (node (ref "U5") (pin "8") (pinfunction "OUT_8") (pintype "output"))
      (node (ref "U6") (pin "2") (pinfunction "B1_2") (pintype "input"))
      (node (ref "U6") (pin "5") (pinfunction "B2_5") (pintype "input"))
      (node (ref "VBIAS") (pin "TP") (pinfunction "TP_TP") (pintype "input"))
    )
    (net (code "18") (name "Net-(C1-Pad1)") (class "Default")
      (node (ref "C1") (pin "1") (pinfunction "1_1") (pintype "passive"))
      (node (ref "R1") (pin "1") (pinfunction "1_1") (pintype "passive"))
    )
    (net (code "19") (name "Net-(CTL_K-S)") (class "Default")
      (node (ref "CTL_K") (pin "2") (pinfunction "S_2") (pintype "passive"))
      (node (ref "R7") (pin "1") (pinfunction "1_1") (pintype "passive"))
    )
    (net (code "20") (name "Net-(D1-PadA)") (class "Default")
      (node (ref "D1") (pin "A") (pinfunction "A_A") (pintype "passive"))
      (node (ref "D5") (pin "C") (pinfunction "C_C") (pintype "passive"))
      (node (ref "Q1") (pin "G") (pinfunction "G_G") (pintype "passive"))
      (node (ref "R2") (pin "2") (pinfunction "2_2") (pintype "passive"))
    )
    (net (code "21") (name "Net-(KILL-PadA)") (class "Default")
      (node (ref "KILL") (pin "A") (pinfunction "A_A") (pintype "passive"))
      (node (ref "R18") (pin "1") (pinfunction "1_1") (pintype "passive"))
    )
    (net (code "22") (name "Net-(PWR-PadA)") (class "Default")
      (node (ref "PWR") (pin "A") (pinfunction "A_A") (pintype "passive"))
      (node (ref "R50") (pin "1") (pinfunction "1_1") (pintype "passive"))
    )
    (net (code "23") (name "Net-(Q2-PadG)") (class "Default")
      (node (ref "Q2") (pin "G") (pinfunction "G_G") (pintype "bidirectional"))
      (node (ref "R10") (pin "2") (pinfunction "2_2") (pintype "passive"))
      (node (ref "R12") (pin "2") (pinfunction "2_2") (pintype "passive"))
      (node (ref "VGATE") (pin "TP") (pinfunction "TP_TP") (pintype "input"))
    )
    (net (code "24") (name "Net-(R17-Pad2)") (class "Default")
      (node (ref "R17") (pin "2") (pinfunction "2_2") (pintype "passive"))
      (node (ref "R21") (pin "1") (pinfunction "1_1") (pintype "passive"))
    )
    (net (code "25") (name "Net-(REF_ADJ-E)") (class "Default")
      (node (ref "R6") (pin "2") (pinfunction "2_2") (pintype "passive"))
      (node (ref "REF_ADJ") (pin "3") (pinfunction "E_3") (pintype "passive"))
    )
    (net (code "26") (name "Net-(REF_ADJ-S)") (class "Default")
      (node (ref "R5") (pin "1") (pinfunction "1_1") (pintype "passive"))
      (node (ref "REF_ADJ") (pin "2") (pinfunction "S_2") (pintype "passive"))
    )
    (net (code "27") (name "Net-(U2-ADJ)") (class "Default")
      (node (ref "C6") (pin "+") (pinfunction "+_+") (pintype "passive"))
      (node (ref "R3") (pin "2") (pinfunction "2_2") (pintype "passive"))
      (node (ref "R4") (pin "1") (pinfunction "1_1") (pintype "passive"))
      (node (ref "U2") (pin "1") (pinfunction "ADJ_1") (pintype "input"))
    )
    (net (code "28") (name "Net-(U3-TRIM)") (class "Default")
      (node (ref "R5") (pin "2") (pinfunction "2_2") (pintype "passive"))
      (node (ref "U3") (pin "5") (pinfunction "TRIM_5") (pintype "passive"))
    )
    (net (code "29") (name "Net-(U5A--IN)") (class "Default")
      (node (ref "R14") (pin "2") (pinfunction "2_2") (pintype "passive"))
      (node (ref "U5") (pin "2") (pinfunction "-IN_2") (pintype "input"))
    )
    (net (code "30") (name "Net-(U5A-OUT)") (class "Default")
      (node (ref "R13") (pin "1") (pinfunction "1_1") (pintype "passive"))
      (node (ref "R14") (pin "1") (pinfunction "1_1") (pintype "passive"))
      (node (ref "R15") (pin "1") (pinfunction "1_1") (pintype "passive"))
      (node (ref "U5") (pin "1") (pinfunction "OUT_1") (pintype "output"))
    )
    (net (code "31") (name "Net-(U5B-+IN)") (class "Default")
      (node (ref "Q2") (pin "S") (pinfunction "S_S") (pintype "bidirectional"))
      (node (ref "RSENSE") (pin "2") (pinfunction "2_2") (pintype "passive"))
      (node (ref "U5") (pin "5") (pinfunction "+IN_5") (pintype "input"))
    )
    (net (code "32") (name "Net-(U5B--IN)") (class "Default")
      (node (ref "R9") (pin "1") (pinfunction "1_1") (pintype "passive"))
      (node (ref "U5") (pin "6") (pinfunction "-IN_6") (pintype "input"))
    )
    (net (code "33") (name "Net-(U5C-+IN)") (class "Default")
      (node (ref "D3") (pin "A") (pinfunction "A_A") (pintype "passive"))
      (node (ref "D4") (pin "C") (pinfunction "C_C") (pintype "passive"))
      (node (ref "R7") (pin "2") (pinfunction "2_2") (pintype "passive"))
      (node (ref "U5") (pin "10") (pinfunction "+IN_10") (pintype "input"))
      (node (ref "U5") (pin "12") (pinfunction "+IN_12") (pintype "input"))
    )
    (net (code "34") (name "Net-(U5C--IN)") (class "Default")
      (node (ref "S4") (pin "2") (pinfunction "2_2") (pintype "passive"))
      (node (ref "U5") (pin "9") (pinfunction "-IN_9") (pintype "input"))
    )
    (net (code "35") (name "Net-(U6-E1)") (class "Default")
      (node (ref "R10") (pin "1") (pinfunction "1_1") (pintype "passive"))
      (node (ref "U6") (pin "4") (pinfunction "E2_4") (pintype "bidirectional"))
      (node (ref "U6") (pin "6") (pinfunction "E1_6") (pintype "bidirectional"))
    )
    (net (code "36") (name "Net-(U8-IN-)") (class "Default")
      (node (ref "R19") (pin "1") (pinfunction "1_1") (pintype "passive"))
      (node (ref "R20") (pin "2") (pinfunction "2_2") (pintype "passive"))
      (node (ref "U8") (pin "4") (pinfunction "IN-_4") (pintype "input"))
    )
    (net (code "37") (name "REFA") (class "Default")
      (node (ref "C2") (pin "1") (pinfunction "1_1") (pintype "passive"))
      (node (ref "REF_ADJ") (pin "1") (pinfunction "A_1") (pintype "passive"))
      (node (ref "U1") (pin "6") (pinfunction "REFA_6") (pintype "input"))
      (node (ref "U3") (pin "4") (pinfunction "VOUT_4") (pintype "output"))
      (node (ref "U5") (pin "3") (pinfunction "+IN_3") (pintype "input"))
      (node (ref "VREF") (pin "TP") (pinfunction "TP_TP") (pintype "input"))
    )
    (net (code "38") (name "REFA2X") (class "Default")
      (node (ref "C16") (pin "1") (pinfunction "1_1") (pintype "passive"))
      (node (ref "R15") (pin "2") (pinfunction "2_2") (pintype "passive"))
      (node (ref "S3") (pin "1") (pinfunction "3_1") (pintype "passive"))
    )
    (net (code "39") (name "SCLK") (class "Default")
      (node (ref "U$1") (pin "SCK") (pinfunction "SCK_SCK") (pintype "passive"))
      (node (ref "U1") (pin "3") (pinfunction "SCK_3") (pintype "input"))
    )
    (net (code "40") (name "SDI") (class "Default")
      (node (ref "U$1") (pin "MOSI") (pinfunction "MOSI_MOSI") (pintype "passive"))
      (node (ref "U1") (pin "4") (pinfunction "SDI_4") (pintype "input"))
    )
    (net (code "41") (name "TEMP") (class "Default")
      (node (ref "U3") (pin "1") (pinfunction "TEMP_1") (pintype "passive"))
      (node (ref "U4") (pin "3") (pinfunction "+IN_3") (pintype "input"))
    )
    (net (code "42") (name "VAUX") (class "Default")
      (node (ref "I/O_BLOCK") (pin "P$9") (pinfunction "9_P$9") (pintype "bidirectional"))
      (node (ref "S4") (pin "3") (pinfunction "3_3") (pintype "passive"))
      (node (ref "VAUX") (pin "1") (pinfunction "1_1") (pintype "passive"))
    )
    (net (code "43") (name "VCTL") (class "Default")
      (node (ref "CTL_K") (pin "1") (pinfunction "A_1") (pintype "passive"))
      (node (ref "S3") (pin "2") (pinfunction "2_2") (pintype "passive"))
    )
    (net (code "44") (name "VCTL_PRE") (class "Default")
      (node (ref "S1") (pin "2") (pinfunction "2_2") (pintype "passive"))
      (node (ref "S3") (pin "3") (pinfunction "1_3") (pintype "passive"))
    )
    (net (code "45") (name "VI") (class "Default")
      (node (ref "I/O_BLOCK") (pin "P$8") (pinfunction "8_P$8") (pintype "bidirectional"))
      (node (ref "R16") (pin "2") (pinfunction "2_2") (pintype "passive"))
      (node (ref "R8") (pin "1") (pinfunction "1_1") (pintype "passive"))
      (node (ref "R9") (pin "2") (pinfunction "2_2") (pintype "passive"))
      (node (ref "S4") (pin "1") (pinfunction "1_1") (pintype "passive"))
      (node (ref "U5") (pin "7") (pinfunction "OUT_7") (pintype "output"))
    )
    (net (code "46") (name "VIN") (class "Default")
      (node (ref "U$1") (pin "VIN") (pinfunction "VIN_VIN") (pintype "power_in"))
    )
    (net (code "47") (name "VINPUT") (class "Default")
      (node (ref "I/O_BLOCK") (pin "P$7") (pinfunction "7_P$7") (pintype "bidirectional"))
      (node (ref "S1") (pin "3") (pinfunction "3_3") (pintype "passive"))
    )
    (net (code "48") (name "VREF") (class "Default")
      (node (ref "I/O_BLOCK") (pin "P$6") (pinfunction "6_P$6") (pintype "bidirectional"))
      (node (ref "U5") (pin "13") (pinfunction "-IN_13") (pintype "input"))
      (node (ref "U5") (pin "14") (pinfunction "OUT_14") (pintype "output"))
    )
    (net (code "49") (name "VTEMP") (class "Default")
      (node (ref "I/O_BLOCK") (pin "P$5") (pinfunction "5_P$5") (pintype "bidirectional"))
      (node (ref "U4") (pin "2") (pinfunction "-IN_2") (pintype "input"))
      (node (ref "U4") (pin "6") (pinfunction "OUT_6") (pintype "output"))
      (node (ref "VTEMP") (pin "TP") (pinfunction "TP_TP") (pintype "input"))
    )
    (net (code "50") (name "unconnected-(U$1-A4{slash}SDA-PadA4)") (class "Default")
      (node (ref "U$1") (pin "A4") (pinfunction "A4/SDA_A4") (pintype "bidirectional"))
    )
    (net (code "51") (name "unconnected-(U$1-A5{slash}SCL-PadA5)") (class "Default")
      (node (ref "U$1") (pin "A5") (pinfunction "A5/SCL_A5") (pintype "bidirectional"))
    )
    (net (code "52") (name "unconnected-(U$1-PadA0)") (class "Default")
      (node (ref "U$1") (pin "A0") (pinfunction "A0_A0") (pintype "bidirectional"))
    )
    (net (code "53") (name "unconnected-(U$1-PadA1)") (class "Default")
      (node (ref "U$1") (pin "A1") (pinfunction "A1_A1") (pintype "bidirectional"))
    )
    (net (code "54") (name "unconnected-(U$1-PadA2)") (class "Default")
      (node (ref "U$1") (pin "A2") (pinfunction "A2_A2") (pintype "bidirectional"))
    )
    (net (code "55") (name "unconnected-(U$1-PadA3)") (class "Default")
      (node (ref "U$1") (pin "A3") (pinfunction "A3_A3") (pintype "bidirectional"))
    )
    (net (code "56") (name "unconnected-(U$1-PadAREF)") (class "Default")
      (node (ref "U$1") (pin "AREF") (pinfunction "AREF_AREF") (pintype "bidirectional"))
    )
    (net (code "57") (name "unconnected-(U$1-PadD5)") (class "Default")
      (node (ref "U$1") (pin "D5") (pinfunction "D5_D5") (pintype "bidirectional"))
    )
    (net (code "58") (name "unconnected-(U$1-PadD6)") (class "Default")
      (node (ref "U$1") (pin "D6") (pinfunction "D6_D6") (pintype "bidirectional"))
    )
    (net (code "59") (name "unconnected-(U$1-PadD7)") (class "Default")
      (node (ref "U$1") (pin "D7") (pinfunction "D7_D7") (pintype "bidirectional"))
    )
    (net (code "60") (name "unconnected-(U$1-PadD8)") (class "Default")
      (node (ref "U$1") (pin "D8") (pinfunction "D8_D8") (pintype "bidirectional"))
    )
    (net (code "61") (name "unconnected-(U$1-PadD9)") (class "Default")
      (node (ref "U$1") (pin "D9") (pinfunction "D9_D9") (pintype "bidirectional"))
    )
    (net (code "62") (name "unconnected-(U$1-PadD10)") (class "Default")
      (node (ref "U$1") (pin "D10") (pinfunction "D10_D10") (pintype "bidirectional"))
    )
    (net (code "63") (name "unconnected-(U$1-PadD11)") (class "Default")
      (node (ref "U$1") (pin "D11") (pinfunction "D11_D11") (pintype "bidirectional"))
    )
    (net (code "64") (name "unconnected-(U$1-PadD12)") (class "Default")
      (node (ref "U$1") (pin "D12") (pinfunction "D12_D12") (pintype "bidirectional"))
    )
    (net (code "65") (name "unconnected-(U$1-PadD13)") (class "Default")
      (node (ref "U$1") (pin "D13") (pinfunction "D13_D13") (pintype "bidirectional"))
    )
    (net (code "66") (name "unconnected-(U$1-PadIOREF)") (class "Default")
      (node (ref "U$1") (pin "IOREF") (pinfunction "IOREF_IOREF") (pintype "output"))
    )
    (net (code "67") (name "unconnected-(U$1-PadMISO)") (class "Default")
      (node (ref "U$1") (pin "MISO") (pinfunction "MISO_MISO") (pintype "passive"))
    )
    (net (code "68") (name "unconnected-(U$1-PadRESERVED)") (class "Default")
      (node (ref "U$1") (pin "RESERVED") (pinfunction "RESERVED_RESERVED") (pintype "no_connect"))
    )
    (net (code "69") (name "unconnected-(U$1-PadSCL)") (class "Default")
      (node (ref "U$1") (pin "SCL") (pinfunction "SCL_SCL") (pintype "bidirectional"))
    )
    (net (code "70") (name "unconnected-(U$1-PadSDA)") (class "Default")
      (node (ref "U$1") (pin "SDA") (pinfunction "SDA_SDA") (pintype "bidirectional"))
    )
    (net (code "71") (name "unconnected-(U$1-RST-PadRESET$1)") (class "Default")
      (node (ref "U$1") (pin "RESET$1") (pinfunction "RST_RESET$1") (pintype "passive"))
    )
    (net (code "72") (name "unconnected-(U$1-{slash}RESET-PadRESET)") (class "Default")
      (node (ref "U$1") (pin "RESET") (pinfunction "/RESET_RESET") (pintype "bidirectional"))
    )
    (net (code "73") (name "unconnected-(U4-NC-Pad1)") (class "Default")
      (node (ref "U4") (pin "1") (pinfunction "NC_1") (pintype "no_connect"))
    )
    (net (code "74") (name "unconnected-(U4-NC_2-Pad5)") (class "Default")
      (node (ref "U4") (pin "5") (pinfunction "NC_2_5") (pintype "no_connect"))
    )
    (net (code "75") (name "unconnected-(U4-NC_3-Pad8)") (class "Default")
      (node (ref "U4") (pin "8") (pinfunction "NC_3_8") (pintype "no_connect"))
    )
  )
)
